# Input_Driver_ADC.net
KiCad netlist of a schematic drawn in Altium Designer
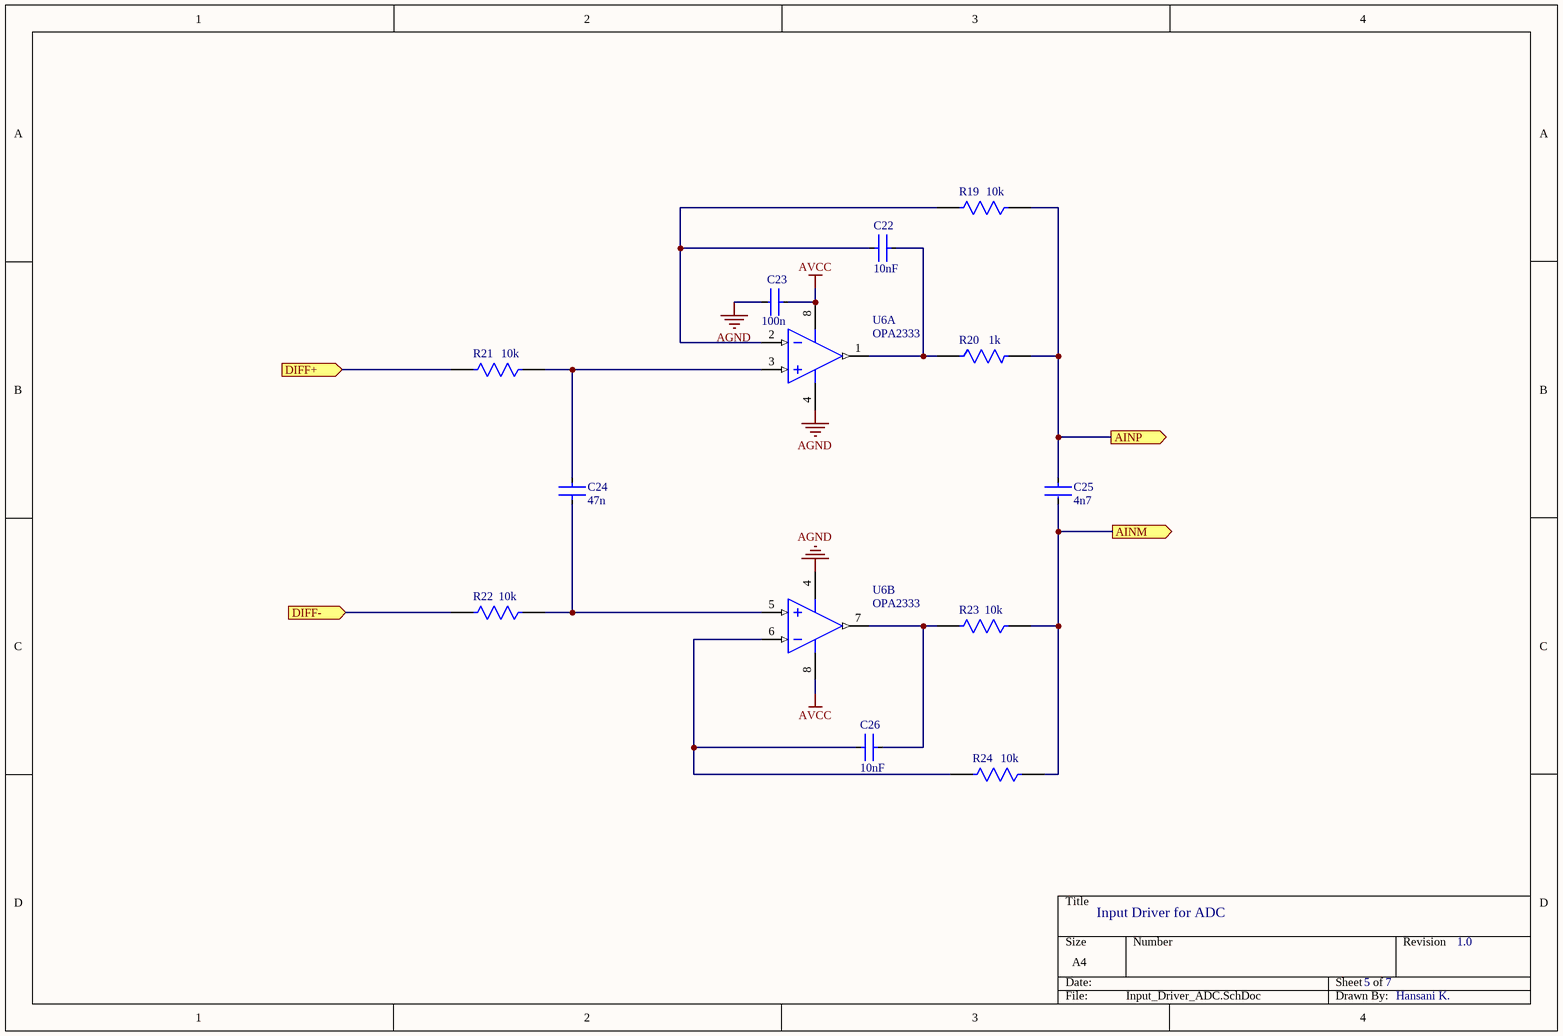
[diagram p0: Input_Driver_ADC.SchDoc]

(export (version "E")
  (design (tool "Eeschema 10.0.6"))
  (components
    (comp (ref "C22")
      (value "10nF")
      (footprint "PCBComponent_1")
      (fields
        (field (name "MANUFACTURER") "Vishay")
        (field (name "MANUFACTURER PART NUMBER") "CDR31BX103AKYRMJ")
        (field (name "TOLERANCE") "10%")
      )
      (libsource (lib "Schlib1") (part "CDR31BX103AKYRMJ"))
    )
    (comp (ref "C23")
      (value "100n")
      (footprint "FP-GRM155-0_05-MFG")
      (description "Chip Multilayer Ceramic Capacitors for General Purpose, 0402, 0.10uF, B, 10%, 20%, 50V")
      (libsource (lib "Altium Content Vault") (part "02cd4be3c70576c341d710602a673aa"))
    )
    (comp (ref "C24")
      (value "47n")
      (footprint "PCBComponent_1")
      (description "Multilayer Ceramic Capacitors MLCC - SMD/SMT 25V 0.047uF C0G 0805 1% AEC-Q200")
      (fields
        (field (name "MANUFACTURER") "KEMET")
        (field (name "MANUFACTURER PART NUMBER") "C0805C473F3GECAUTO7210")
      )
      (libsource (lib "Schlib1") (part "C0805C473F3GECAUTO7210"))
    )
    (comp (ref "C25")
      (value "4n7")
      (footprint "FP-AC0805-0_85-MFG")
      (description "CAP CER 4700PF 100V X7R 0805")
      (fields (field (name "TOLERANCE") "0.1") (field (name "MANUFACTURER") "Yageo"))
      (libsource (lib "Altium Content Vault") (part "11868f565c42a9108669ba33697ecf6"))
    )
    (comp (ref "C26")
      (value "10nF")
      (footprint "PCBComponent_1")
      (fields
        (field (name "MANUFACTURER") "Vishay")
        (field (name "MANUFACTURER PART NUMBER") "CDR31BX103AKYRMJ")
        (field (name "TOLERANCE") "10%")
      )
      (libsource (lib "Schlib1") (part "CDR31BX103AKYRMJ"))
    )
    (comp (ref "R19")
      (value "10k")
      (footprint "FP-CRGCQ0805-IPC_C")
      (description "CRGCQ 0805 10K 5%")
      (fields
        (field (name "MANUFACTURER PART NUMBER") "CRGCQ0805J10K")
        (field (name "MANUFACTURER") "TE Connectivity")
      )
      (libsource (lib "Altium Content Vault") (part "1029c3af85768c4190bb7ad29bc67b5"))
    )
    (comp (ref "R20")
      (value "1k")
      (footprint "FP-PATT0805-MFG")
      (description "RES SMD 1K OHM 0.1% 1/5W 0805")
      (fields (field (name "TOLERANCE") "0.1%") (field (name "MANUFACTURER PART NUMBER") "PATT0805E1001BGT1"))
      (libsource (lib "Altium Content Vault") (part "1029c3af85768c4190bb7ad29bc67b5"))
    )
    (comp (ref "R21")
      (value "10k")
      (footprint "FP-CRGCQ0805-IPC_C")
      (description "CRGCQ 0805 10K 5%")
      (fields
        (field (name "MANUFACTURER PART NUMBER") "CRGCQ0805J10K")
        (field (name "MANUFACTURER") "TE Connectivity")
      )
      (libsource (lib "Altium Content Vault") (part "1029c3af85768c4190bb7ad29bc67b5"))
    )
    (comp (ref "R22")
      (value "10k")
      (footprint "FP-CRGCQ0805-IPC_C")
      (description "CRGCQ 0805 10K 5%")
      (fields
        (field (name "MANUFACTURER PART NUMBER") "CRGCQ0805J10K")
        (field (name "MANUFACTURER") "TE Connectivity")
      )
      (libsource (lib "Altium Content Vault") (part "1029c3af85768c4190bb7ad29bc67b5"))
    )
    (comp (ref "R23")
      (value "10k")
      (footprint "FP-CRGCQ0805-IPC_C")
      (description "CRGCQ 0805 10K 5%")
      (fields
        (field (name "MANUFACTURER PART NUMBER") "CRGCQ0805J10K")
        (field (name "MANUFACTURER") "TE Connectivity")
      )
      (libsource (lib "Altium Content Vault") (part "1029c3af85768c4190bb7ad29bc67b5"))
    )
    (comp (ref "R24")
      (value "10k")
      (footprint "FP-CRGCQ0805-IPC_C")
      (description "CRGCQ 0805 10K 5%")
      (fields
        (field (name "MANUFACTURER PART NUMBER") "CRGCQ0805J10K")
        (field (name "MANUFACTURER") "TE Connectivity")
      )
      (libsource (lib "Altium Content Vault") (part "1029c3af85768c4190bb7ad29bc67b5"))
    )
    (comp (ref "U6")
      (value "OPA2333")
      (footprint "DGK0008A_M")
      (fields (field (name "MANUFACTURER") "Texas Instruments") (field (name "PARTNUMBER") "OPA2333AIDGKR"))
      (libsource (lib "Altium Content Vault") (part "TI-OPA-8_2"))
    )
  )
  (nets
    (net (code "1") (name "/AINM") (class "Default")
      (node (ref "C25") (pin "2") (pinfunction "2_2") (pintype "passive"))
      (node (ref "R23") (pin "1") (pinfunction "1_1") (pintype "passive"))
      (node (ref "R24") (pin "1") (pinfunction "1_1") (pintype "passive"))
    )
    (net (code "2") (name "/AINP") (class "Default")
      (node (ref "C25") (pin "1") (pinfunction "1_1") (pintype "passive"))
      (node (ref "R19") (pin "1") (pinfunction "1_1") (pintype "passive"))
      (node (ref "R20") (pin "2") (pinfunction "2_2") (pintype "passive"))
    )
    (net (code "3") (name "/DIFF+") (class "Default")
      (node (ref "R21") (pin "2") (pinfunction "2_2") (pintype "passive"))
    )
    (net (code "4") (name "/DIFF-") (class "Default")
      (node (ref "R22") (pin "2") (pinfunction "2_2") (pintype "passive"))
    )
    (net (code "5") (name "AGND") (class "Default")
      (node (ref "C23") (pin "2") (pinfunction "2_2") (pintype "passive"))
      (node (ref "U6") (pin "4") (pinfunction "V-_4") (pintype "power_in"))
    )
    (net (code "6") (name "AVCC") (class "Default")
      (node (ref "C23") (pin "1") (pinfunction "1_1") (pintype "passive"))
      (node (ref "U6") (pin "8") (pinfunction "V+_8") (pintype "power_in"))
    )
    (net (code "7") (name "Net-(U6A-IN_A+)") (class "Default")
      (node (ref "C24") (pin "1") (pinfunction "1_1") (pintype "passive"))
      (node (ref "R21") (pin "1") (pinfunction "1_1") (pintype "passive"))
      (node (ref "U6") (pin "3") (pinfunction "IN_A+_3") (pintype "input"))
    )
    (net (code "8") (name "Net-(U6A-IN_A-)") (class "Default")
      (node (ref "C22") (pin "1") (pinfunction "1_1") (pintype "passive"))
      (node (ref "R19") (pin "2") (pinfunction "2_2") (pintype "passive"))
      (node (ref "U6") (pin "2") (pinfunction "IN_A-_2") (pintype "input"))
    )
    (net (code "9") (name "Net-(U6A-OUT_A)") (class "Default")
      (node (ref "C22") (pin "2") (pinfunction "2_2") (pintype "passive"))
      (node (ref "R20") (pin "1") (pinfunction "1_1") (pintype "passive"))
      (node (ref "U6") (pin "1") (pinfunction "OUT_A_1") (pintype "output"))
    )
    (net (code "10") (name "Net-(U6B-IN_B+)") (class "Default")
      (node (ref "C24") (pin "2") (pinfunction "2_2") (pintype "passive"))
      (node (ref "R22") (pin "1") (pinfunction "1_1") (pintype "passive"))
      (node (ref "U6") (pin "5") (pinfunction "IN_B+_5") (pintype "input"))
    )
    (net (code "11") (name "Net-(U6B-IN_B-)") (class "Default")
      (node (ref "C26") (pin "1") (pinfunction "1_1") (pintype "passive"))
      (node (ref "R24") (pin "2") (pinfunction "2_2") (pintype "passive"))
      (node (ref "U6") (pin "6") (pinfunction "IN_B-_6") (pintype "input"))
    )
    (net (code "12") (name "Net-(U6B-OUT_B)") (class "Default")
      (node (ref "C26") (pin "2") (pinfunction "2_2") (pintype "passive"))
      (node (ref "R23") (pin "2") (pinfunction "2_2") (pintype "passive"))
      (node (ref "U6") (pin "7") (pinfunction "OUT_B_7") (pintype "output"))
    )
  )
)
